# Main.net
KiCad netlist of a schematic drawn in Altium Designer
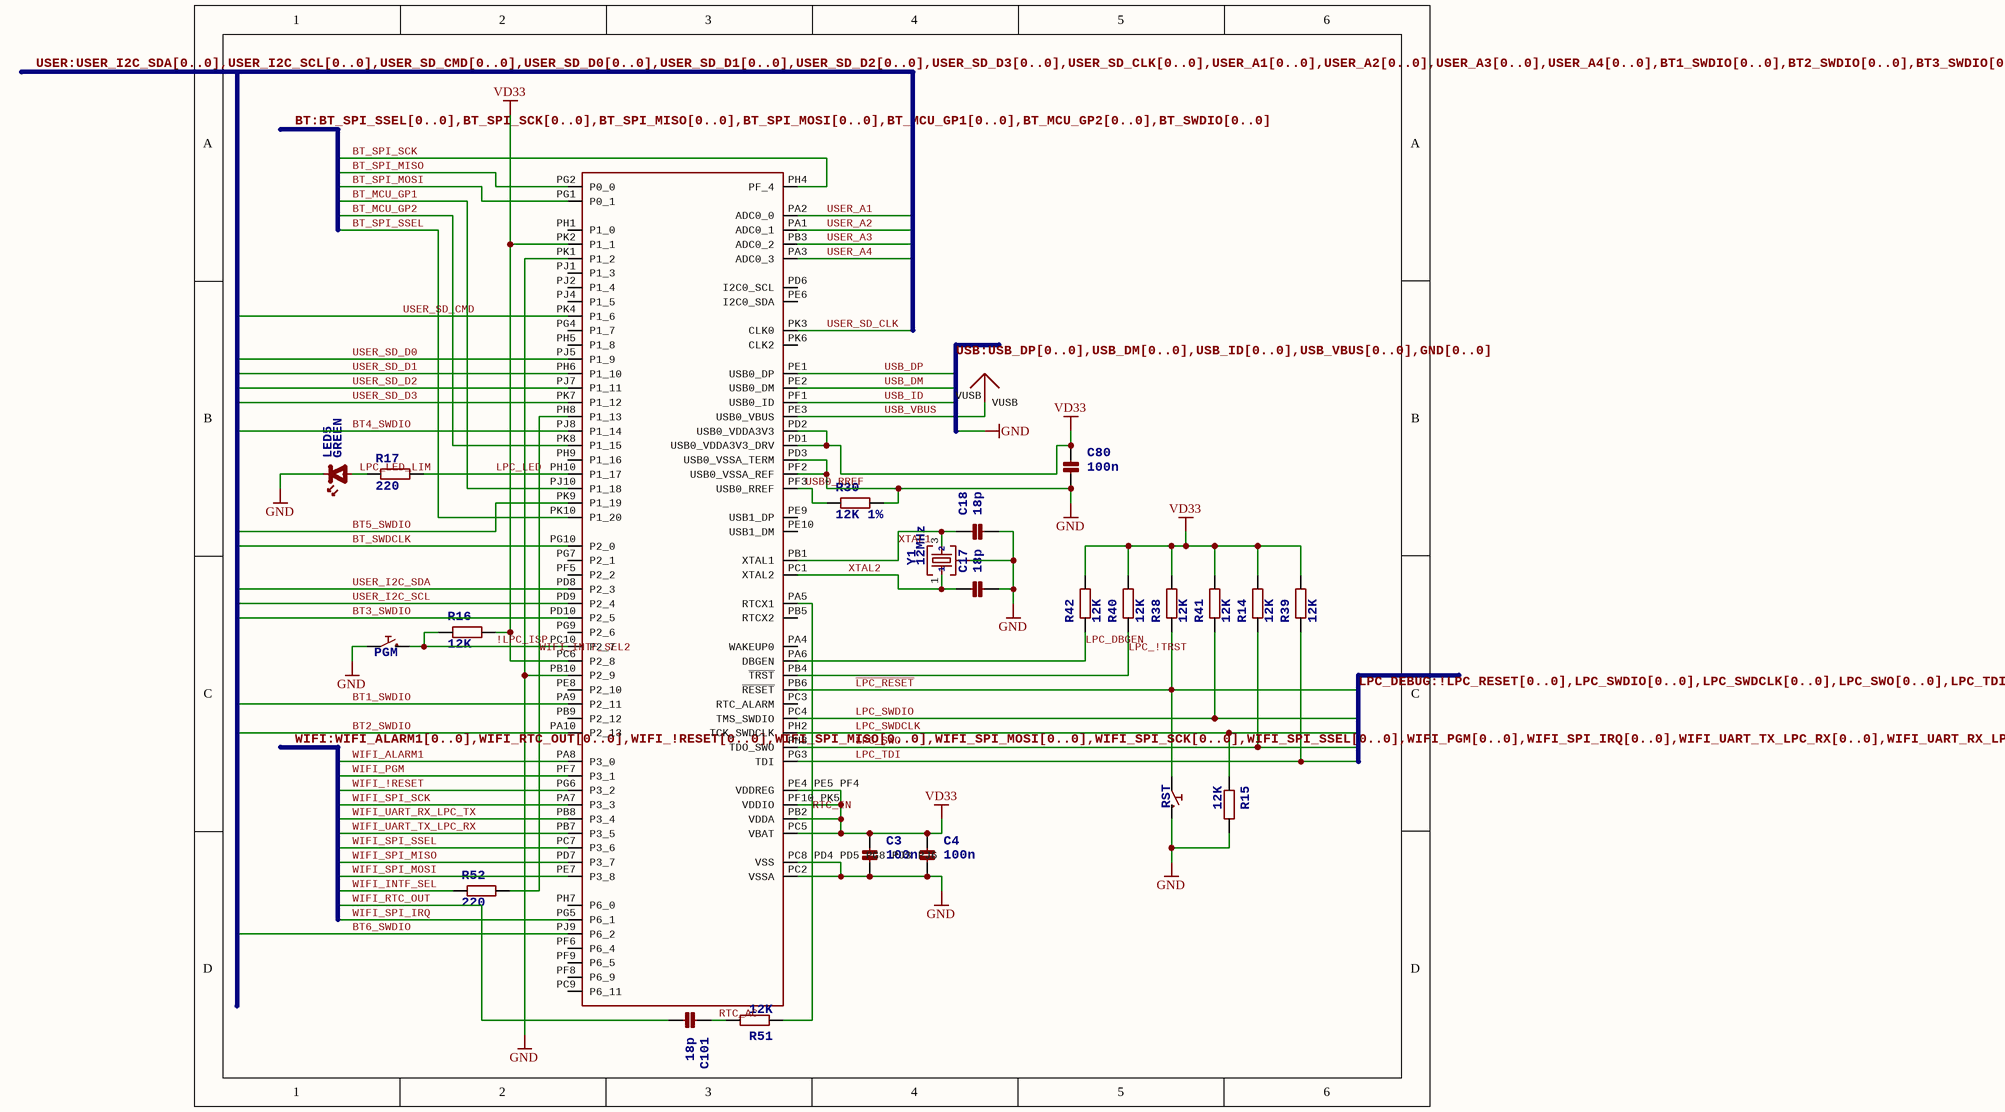
[diagram p0: Main.SchDoc]

(export (version "E")
  (design (tool "Eeschema 10.0.6"))
  (components
    (comp (ref "C3") (value "100n") (footprint "0402") (libsource (lib "") (part "CAP_CERAMIC0402_1")))
    (comp (ref "C4") (value "100n") (footprint "0402") (libsource (lib "") (part "CAP_CERAMIC0402_1")))
    (comp (ref "C17") (value "18p") (footprint "0402") (libsource (lib "anykey") (part "CAP_CERAMIC0402")))
    (comp (ref "C18") (value "18p") (footprint "0402") (libsource (lib "anykey") (part "CAP_CERAMIC0402")))
    (comp (ref "C80") (value "100n") (footprint "0402") (libsource (lib "") (part "CAP_CERAMIC0402_1")))
    (comp (ref "C101") (value "18p") (footprint "0402") (libsource (lib "") (part "CAP_CERAMIC0402_2")))
    (comp (ref "LED5")
      (value "GREEN")
      (footprint "0402_POLAR")
      (description "LED common")
      (libsource (lib "anykey") (part "LED0402"))
    )
    (comp (ref "MCU1")
      (value "LPC1837JET100TFBGA100(JET100)")
      (footprint "BGA100-0.8")
      (libsource (lib "anykey") (part "LPC1837JET100TFBGA100(JET100)"))
    )
    (comp (ref "PGM")
      (value "PUSHBUTTONKMR2XX")
      (footprint "CK-KMR2")
      (description "<p><b>Push button</b> 1 x momentary close switches</p>")
      (libsource (lib "anykey") (part "PUSHBUTTONKMR2XX"))
    )
    (comp (ref "R14")
      (value "12K")
      (footprint "0402")
      (description "<B>RESISTOR</B>, European symbol")
      (libsource (lib "anykey") (part "R-EU_0402"))
    )
    (comp (ref "R15")
      (value "12K")
      (footprint "0402")
      (description "<B>RESISTOR</B>, European symbol")
      (libsource (lib "anykey") (part "R-EU_0402"))
    )
    (comp (ref "R16")
      (value "12K")
      (footprint "0402")
      (description "<B>RESISTOR</B>, European symbol")
      (libsource (lib "anykey") (part "R-EU_0402"))
    )
    (comp (ref "R17")
      (value "220")
      (footprint "0402")
      (description "<B>RESISTOR</B>, European symbol")
      (libsource (lib "anykey") (part "R-EU_0402"))
    )
    (comp (ref "R30")
      (value "12K 1%")
      (footprint "0402")
      (description "<B>RESISTOR</B>, European symbol")
      (libsource (lib "anykey") (part "R-EU_0402"))
    )
    (comp (ref "R38")
      (value "12K")
      (footprint "0402")
      (description "<B>RESISTOR</B>, European symbol")
      (libsource (lib "anykey") (part "R-EU_0402"))
    )
    (comp (ref "R39")
      (value "12K")
      (footprint "0402")
      (description "<B>RESISTOR</B>, European symbol")
      (libsource (lib "anykey") (part "R-EU_0402"))
    )
    (comp (ref "R40")
      (value "12K")
      (footprint "0402")
      (description "<B>RESISTOR</B>, European symbol")
      (libsource (lib "anykey") (part "R-EU_0402"))
    )
    (comp (ref "R41")
      (value "12K")
      (footprint "0402")
      (description "<B>RESISTOR</B>, European symbol")
      (libsource (lib "anykey") (part "R-EU_0402"))
    )
    (comp (ref "R42")
      (value "12K")
      (footprint "0402")
      (description "<B>RESISTOR</B>, European symbol")
      (libsource (lib "anykey") (part "R-EU_0402"))
    )
    (comp (ref "R51")
      (value "12K")
      (footprint "0402")
      (description "<B>RESISTOR</B>, European symbol")
      (libsource (lib "anykey") (part "R-EU_0402"))
    )
    (comp (ref "R52")
      (value "220")
      (footprint "0402")
      (description "<B>RESISTOR</B>, European symbol")
      (libsource (lib "anykey") (part "R-EU_0402"))
    )
    (comp (ref "RST")
      (value "PUSHBUTTONKMR2XX")
      (footprint "CK-KMR2")
      (description "<p><b>Push button</b> 1 x momentary close switches</p>")
      (libsource (lib "anykey") (part "PUSHBUTTONKMR2XX"))
    )
    (comp (ref "U$31") (value "VUSB") (description "\"USB Power\"") (libsource (lib "anykey") (part "VUSB")))
    (comp (ref "Y1")
      (value "12MHz")
      (footprint "ABM8G")
      (fields (field (name "1") "1") (field (name "2") "2"))
      (libsource (lib "anykey") (part "CRYSTAL_WITH_GROUNDABM8G"))
    )
  )
  (nets
    (net (code "6") (name "/!LPC_ISP") (class "Default")
      (node (ref "MCU1") (pin "PC10") (pinfunction "P2_7_PC10") (pintype "passive"))
      (node (ref "PGM") (pin "P$3_P$4") (pinfunction "2_P$3_P$4") (pintype "passive"))
      (node (ref "R16") (pin "P$1") (pinfunction "1_P$1") (pintype "passive"))
    )
    (net (code "7") (name "/BT1_SWDIO") (class "Default")
      (node (ref "MCU1") (pin "PA9") (pinfunction "P2_11_PA9") (pintype "passive"))
    )
    (net (code "8") (name "/BT2_SWDIO") (class "Default")
      (node (ref "MCU1") (pin "PA10") (pinfunction "P2_13_PA10") (pintype "passive"))
    )
    (net (code "9") (name "/BT3_SWDIO") (class "Default")
      (node (ref "MCU1") (pin "PD10") (pinfunction "P2_5_PD10") (pintype "passive"))
    )
    (net (code "10") (name "/BT4_SWDIO") (class "Default")
      (node (ref "MCU1") (pin "PJ8") (pinfunction "P1_14_PJ8") (pintype "passive"))
    )
    (net (code "11") (name "/BT5_SWDIO") (class "Default")
      (node (ref "MCU1") (pin "PK9") (pinfunction "P1_19_PK9") (pintype "passive"))
    )
    (net (code "12") (name "/BT6_SWDIO") (class "Default")
      (node (ref "MCU1") (pin "PJ9") (pinfunction "P6_2_PJ9") (pintype "passive"))
    )
    (net (code "13") (name "/BT_MCU_GP1") (class "Default")
      (node (ref "MCU1") (pin "PJ10") (pinfunction "P1_18_PJ10") (pintype "passive"))
    )
    (net (code "14") (name "/BT_MCU_GP2") (class "Default")
      (node (ref "MCU1") (pin "PK8") (pinfunction "P1_15_PK8") (pintype "passive"))
    )
    (net (code "15") (name "/BT_SPI_MISO") (class "Default")
      (node (ref "MCU1") (pin "PG2") (pinfunction "P0_0_PG2") (pintype "passive"))
    )
    (net (code "16") (name "/BT_SPI_MOSI") (class "Default")
      (node (ref "MCU1") (pin "PG1") (pinfunction "P0_1_PG1") (pintype "passive"))
    )
    (net (code "17") (name "/BT_SPI_SCK") (class "Default")
      (node (ref "MCU1") (pin "PH4") (pinfunction "PF_4_PH4") (pintype "passive"))
    )
    (net (code "18") (name "/BT_SPI_SSEL") (class "Default")
      (node (ref "MCU1") (pin "PK10") (pinfunction "P1_20_PK10") (pintype "passive"))
    )
    (net (code "19") (name "/BT_SWDCLK") (class "Default")
      (node (ref "MCU1") (pin "PG10") (pinfunction "P2_0_PG10") (pintype "passive"))
    )
    (net (code "20") (name "/LPC_!TRST") (class "Default")
      (node (ref "MCU1") (pin "PB4") (pinfunction "~{TRST}_PB4") (pintype "passive"))
      (node (ref "R40") (pin "P$1") (pinfunction "1_P$1") (pintype "passive"))
    )
    (net (code "21") (name "/LPC_DBGEN") (class "Default")
      (node (ref "MCU1") (pin "PA6") (pinfunction "DBGEN_PA6") (pintype "passive"))
      (node (ref "R42") (pin "P$1") (pinfunction "1_P$1") (pintype "passive"))
    )
    (net (code "22") (name "/LPC_LED") (class "Default")
      (node (ref "MCU1") (pin "PH10") (pinfunction "P1_17_PH10") (pintype "passive"))
      (node (ref "R17") (pin "P$2") (pinfunction "2_P$2") (pintype "passive"))
    )
    (net (code "23") (name "/LPC_LED_LIM") (class "Default")
      (node (ref "LED5") (pin "A") (pinfunction "ANODE_A") (pintype "passive"))
      (node (ref "R17") (pin "P$1") (pinfunction "1_P$1") (pintype "passive"))
    )
    (net (code "24") (name "/LPC_SWDCLK") (class "Default")
      (node (ref "MCU1") (pin "PH2") (pinfunction "TCK_SWDCLK_PH2") (pintype "passive"))
      (node (ref "R15") (pin "P$1") (pinfunction "1_P$1") (pintype "passive"))
    )
    (net (code "25") (name "/LPC_SWDIO") (class "Default")
      (node (ref "MCU1") (pin "PC4") (pinfunction "TMS_SWDIO_PC4") (pintype "passive"))
      (node (ref "R41") (pin "P$1") (pinfunction "1_P$1") (pintype "passive"))
    )
    (net (code "26") (name "/LPC_SWO") (class "Default")
      (node (ref "MCU1") (pin "PH3") (pinfunction "TDO_SWO_PH3") (pintype "passive"))
      (node (ref "R14") (pin "P$1") (pinfunction "1_P$1") (pintype "passive"))
    )
    (net (code "27") (name "/LPC_TDI") (class "Default")
      (node (ref "MCU1") (pin "PG3") (pinfunction "TDI_PG3") (pintype "passive"))
      (node (ref "R39") (pin "P$1") (pinfunction "1_P$1") (pintype "passive"))
    )
    (net (code "28") (name "/RTC_AC") (class "Default")
      (node (ref "C101") (pin "P$1") (pinfunction "P$1_P$1") (pintype "passive"))
      (node (ref "R51") (pin "P$2") (pinfunction "2_P$2") (pintype "passive"))
    )
    (net (code "29") (name "/RTC_IN") (class "Default")
      (node (ref "MCU1") (pin "PA5") (pinfunction "RTCX1_PA5") (pintype "passive"))
      (node (ref "R51") (pin "P$1") (pinfunction "1_P$1") (pintype "passive"))
    )
    (net (code "30") (name "/USB0_RREF") (class "Default")
      (node (ref "MCU1") (pin "PF3") (pinfunction "USB0_RREF_PF3") (pintype "passive"))
      (node (ref "R30") (pin "P$1") (pinfunction "1_P$1") (pintype "passive"))
    )
    (net (code "31") (name "/USB_DM") (class "Default")
      (node (ref "MCU1") (pin "PE2") (pinfunction "USB0_DM_PE2") (pintype "passive"))
    )
    (net (code "32") (name "/USB_DP") (class "Default")
      (node (ref "MCU1") (pin "PE1") (pinfunction "USB0_DP_PE1") (pintype "passive"))
    )
    (net (code "33") (name "/USB_ID") (class "Default")
      (node (ref "MCU1") (pin "PF1") (pinfunction "USB0_ID_PF1") (pintype "passive"))
    )
    (net (code "34") (name "/USB_VBUS") (class "Default")
      (node (ref "MCU1") (pin "PE3") (pinfunction "USB0_VBUS_PE3") (pintype "passive"))
      (node (ref "U$31") (pin "VUSB") (pinfunction "VUSB_VUSB") (pintype "open_emitter"))
    )
    (net (code "35") (name "/USER_A1") (class "Default")
      (node (ref "MCU1") (pin "PA2") (pinfunction "ADC0_0_PA2") (pintype "passive"))
    )
    (net (code "36") (name "/USER_A2") (class "Default")
      (node (ref "MCU1") (pin "PA1") (pinfunction "ADC0_1_PA1") (pintype "passive"))
    )
    (net (code "37") (name "/USER_A3") (class "Default")
      (node (ref "MCU1") (pin "PB3") (pinfunction "ADC0_2_PB3") (pintype "passive"))
    )
    (net (code "38") (name "/USER_A4") (class "Default")
      (node (ref "MCU1") (pin "PA3") (pinfunction "ADC0_3_PA3") (pintype "passive"))
    )
    (net (code "39") (name "/USER_I2C_SCL") (class "Default")
      (node (ref "MCU1") (pin "PD9") (pinfunction "P2_4_PD9") (pintype "passive"))
    )
    (net (code "40") (name "/USER_I2C_SDA") (class "Default")
      (node (ref "MCU1") (pin "PD8") (pinfunction "P2_3_PD8") (pintype "passive"))
    )
    (net (code "41") (name "/USER_SD_CLK") (class "Default")
      (node (ref "MCU1") (pin "PK3") (pinfunction "CLK0_PK3") (pintype "passive"))
    )
    (net (code "42") (name "/USER_SD_CMD") (class "Default")
      (node (ref "MCU1") (pin "PK4") (pinfunction "P1_6_PK4") (pintype "passive"))
    )
    (net (code "43") (name "/USER_SD_D0") (class "Default")
      (node (ref "MCU1") (pin "PJ5") (pinfunction "P1_9_PJ5") (pintype "passive"))
    )
    (net (code "44") (name "/USER_SD_D1") (class "Default")
      (node (ref "MCU1") (pin "PH6") (pinfunction "P1_10_PH6") (pintype "passive"))
    )
    (net (code "45") (name "/USER_SD_D2") (class "Default")
      (node (ref "MCU1") (pin "PJ7") (pinfunction "P1_11_PJ7") (pintype "passive"))
    )
    (net (code "46") (name "/USER_SD_D3") (class "Default")
      (node (ref "MCU1") (pin "PK7") (pinfunction "P1_12_PK7") (pintype "passive"))
    )
    (net (code "47") (name "/WIFI_!RESET") (class "Default")
      (node (ref "MCU1") (pin "PG6") (pinfunction "P3_2_PG6") (pintype "passive"))
    )
    (net (code "48") (name "/WIFI_ALARM1") (class "Default")
      (node (ref "MCU1") (pin "PA8") (pinfunction "P3_0_PA8") (pintype "passive"))
    )
    (net (code "49") (name "/WIFI_INTF_SEL") (class "Default")
      (node (ref "R52") (pin "P$1") (pinfunction "1_P$1") (pintype "passive"))
    )
    (net (code "50") (name "/WIFI_INTF_SEL2") (class "Default")
      (node (ref "MCU1") (pin "PH8") (pinfunction "P1_13_PH8") (pintype "passive"))
      (node (ref "R52") (pin "P$2") (pinfunction "2_P$2") (pintype "passive"))
    )
    (net (code "51") (name "/WIFI_PGM") (class "Default")
      (node (ref "MCU1") (pin "PF7") (pinfunction "P3_1_PF7") (pintype "passive"))
    )
    (net (code "52") (name "/WIFI_RTC_OUT") (class "Default")
      (node (ref "C101") (pin "P$2") (pinfunction "P$2_P$2") (pintype "passive"))
    )
    (net (code "53") (name "/WIFI_SPI_IRQ") (class "Default")
      (node (ref "MCU1") (pin "PG5") (pinfunction "P6_1_PG5") (pintype "passive"))
    )
    (net (code "54") (name "/WIFI_SPI_MISO") (class "Default")
      (node (ref "MCU1") (pin "PD7") (pinfunction "P3_7_PD7") (pintype "passive"))
    )
    (net (code "55") (name "/WIFI_SPI_MOSI") (class "Default")
      (node (ref "MCU1") (pin "PE7") (pinfunction "P3_8_PE7") (pintype "passive"))
    )
    (net (code "56") (name "/WIFI_SPI_SCK") (class "Default")
      (node (ref "MCU1") (pin "PA7") (pinfunction "P3_3_PA7") (pintype "passive"))
    )
    (net (code "57") (name "/WIFI_SPI_SSEL") (class "Default")
      (node (ref "MCU1") (pin "PC7") (pinfunction "P3_6_PC7") (pintype "passive"))
    )
    (net (code "58") (name "/WIFI_UART_RX_LPC_TX") (class "Default")
      (node (ref "MCU1") (pin "PB8") (pinfunction "P3_4_PB8") (pintype "passive"))
    )
    (net (code "59") (name "/WIFI_UART_TX_LPC_RX") (class "Default")
      (node (ref "MCU1") (pin "PB7") (pinfunction "P3_5_PB7") (pintype "passive"))
    )
    (net (code "60") (name "/XTAL1") (class "Default")
      (node (ref "C18") (pin "P$1") (pinfunction "P$1_P$1") (pintype "passive"))
      (node (ref "MCU1") (pin "PB1") (pinfunction "XTAL1_PB1") (pintype "passive"))
      (node (ref "Y1") (pin "3") (pinfunction "2_3") (pintype "passive"))
    )
    (net (code "61") (name "/XTAL2") (class "Default")
      (node (ref "C17") (pin "P$1") (pinfunction "P$1_P$1") (pintype "passive"))
      (node (ref "MCU1") (pin "PC1") (pinfunction "XTAL2_PC1") (pintype "passive"))
      (node (ref "Y1") (pin "1") (pinfunction "1_1") (pintype "passive"))
    )
    (net (code "63") (name "/{\"LPC_DEBUG:!LPC_RESET[0..0],LPC_SWDIO[0..0],LPC_SWDCLK[0..0],LPC_SWO[0..0],LPC_TDI[0..0]\"}") (class "Default")
      (node (ref "MCU1") (pin "PB6") (pinfunction "~{RESET}_PB6") (pintype "passive"))
      (node (ref "R38") (pin "P$1") (pinfunction "1_P$1") (pintype "passive"))
      (node (ref "RST") (pin "P$1_P$2") (pinfunction "1_P$1_P$2") (pintype "passive"))
    )
    (net (code "67") (name "GND") (class "Default")
      (node (ref "C17") (pin "P$2") (pinfunction "P$2_P$2") (pintype "passive"))
      (node (ref "C18") (pin "P$2") (pinfunction "P$2_P$2") (pintype "passive"))
      (node (ref "C3") (pin "P$2") (pinfunction "P$2_P$2") (pintype "passive"))
      (node (ref "C4") (pin "P$2") (pinfunction "P$2_P$2") (pintype "passive"))
      (node (ref "C80") (pin "P$2") (pinfunction "P$2_P$2") (pintype "passive"))
      (node (ref "LED5") (pin "K") (pinfunction "CATHODE_K") (pintype "passive"))
      (node (ref "MCU1") (pin "PB10") (pinfunction "P2_9_PB10") (pintype "passive"))
      (node (ref "MCU1") (pin "PC2") (pinfunction "VSSA_PC2") (pintype "passive"))
      (node (ref "MCU1") (pin "PC8_PD4_PD5_PG8_PJ3_PJ6") (pinfunction "VSS_PC8_PD4_PD5_PG8_PJ3_PJ6") (pintype "passive"))
      (node (ref "MCU1") (pin "PD3") (pinfunction "USB0_VSSA_TERM_PD3") (pintype "power_in"))
      (node (ref "MCU1") (pin "PF2") (pinfunction "USB0_VSSA_REF_PF2") (pintype "power_in"))
      (node (ref "MCU1") (pin "PK1") (pinfunction "P1_2_PK1") (pintype "passive"))
      (node (ref "PGM") (pin "P$1_P$2") (pinfunction "1_P$1_P$2") (pintype "passive"))
      (node (ref "R15") (pin "P$2") (pinfunction "2_P$2") (pintype "passive"))
      (node (ref "R30") (pin "P$2") (pinfunction "2_P$2") (pintype "passive"))
      (node (ref "RST") (pin "P$3_P$4") (pinfunction "2_P$3_P$4") (pintype "passive"))
      (node (ref "Y1") (pin "2_4") (pinfunction "GND_2_4") (pintype "power_in"))
    )
    (net (code "68") (name "VD33") (class "Default")
      (node (ref "C3") (pin "P$1") (pinfunction "P$1_P$1") (pintype "passive"))
      (node (ref "C4") (pin "P$1") (pinfunction "P$1_P$1") (pintype "passive"))
      (node (ref "C80") (pin "P$1") (pinfunction "P$1_P$1") (pintype "passive"))
      (node (ref "MCU1") (pin "PB2") (pinfunction "VDDA_PB2") (pintype "passive"))
      (node (ref "MCU1") (pin "PC5") (pinfunction "VBAT_PC5") (pintype "passive"))
      (node (ref "MCU1") (pin "PC6") (pinfunction "P2_8_PC6") (pintype "passive"))
      (node (ref "MCU1") (pin "PD1") (pinfunction "USB0_VDDA3V3_DRV_PD1") (pintype "power_in"))
      (node (ref "MCU1") (pin "PD2") (pinfunction "USB0_VDDA3V3_PD2") (pintype "power_in"))
      (node (ref "MCU1") (pin "PE4_PE5_PF4") (pinfunction "VDDREG_PE4_PE5_PF4") (pintype "passive"))
      (node (ref "MCU1") (pin "PF10_PK5") (pinfunction "VDDIO_PF10_PK5") (pintype "passive"))
      (node (ref "MCU1") (pin "PK2") (pinfunction "P1_1_PK2") (pintype "passive"))
      (node (ref "R14") (pin "P$2") (pinfunction "2_P$2") (pintype "passive"))
      (node (ref "R16") (pin "P$2") (pinfunction "2_P$2") (pintype "passive"))
      (node (ref "R38") (pin "P$2") (pinfunction "2_P$2") (pintype "passive"))
      (node (ref "R39") (pin "P$2") (pinfunction "2_P$2") (pintype "passive"))
      (node (ref "R40") (pin "P$2") (pinfunction "2_P$2") (pintype "passive"))
      (node (ref "R41") (pin "P$2") (pinfunction "2_P$2") (pintype "passive"))
      (node (ref "R42") (pin "P$2") (pinfunction "2_P$2") (pintype "passive"))
    )
    (net (code "69") (name "unconnected-(MCU1-CLK2-PadPK6)") (class "Default")
      (node (ref "MCU1") (pin "PK6") (pinfunction "CLK2_PK6") (pintype "passive"))
    )
    (net (code "70") (name "unconnected-(MCU1-I2C0_SCL-PadPD6)") (class "Default")
      (node (ref "MCU1") (pin "PD6") (pinfunction "I2C0_SCL_PD6") (pintype "passive"))
    )
    (net (code "71") (name "unconnected-(MCU1-I2C0_SDA-PadPE6)") (class "Default")
      (node (ref "MCU1") (pin "PE6") (pinfunction "I2C0_SDA_PE6") (pintype "passive"))
    )
    (net (code "72") (name "unconnected-(MCU1-P1_0-PadPH1)") (class "Default")
      (node (ref "MCU1") (pin "PH1") (pinfunction "P1_0_PH1") (pintype "passive"))
    )
    (net (code "73") (name "unconnected-(MCU1-P1_3-PadPJ1)") (class "Default")
      (node (ref "MCU1") (pin "PJ1") (pinfunction "P1_3_PJ1") (pintype "passive"))
    )
    (net (code "74") (name "unconnected-(MCU1-P1_4-PadPJ2)") (class "Default")
      (node (ref "MCU1") (pin "PJ2") (pinfunction "P1_4_PJ2") (pintype "passive"))
    )
    (net (code "75") (name "unconnected-(MCU1-P1_5-PadPJ4)") (class "Default")
      (node (ref "MCU1") (pin "PJ4") (pinfunction "P1_5_PJ4") (pintype "passive"))
    )
    (net (code "76") (name "unconnected-(MCU1-P1_7-PadPG4)") (class "Default")
      (node (ref "MCU1") (pin "PG4") (pinfunction "P1_7_PG4") (pintype "passive"))
    )
    (net (code "77") (name "unconnected-(MCU1-P1_8-PadPH5)") (class "Default")
      (node (ref "MCU1") (pin "PH5") (pinfunction "P1_8_PH5") (pintype "passive"))
    )
    (net (code "78") (name "unconnected-(MCU1-P1_16-PadPH9)") (class "Default")
      (node (ref "MCU1") (pin "PH9") (pinfunction "P1_16_PH9") (pintype "passive"))
    )
    (net (code "79") (name "unconnected-(MCU1-P2_1-PadPG7)") (class "Default")
      (node (ref "MCU1") (pin "PG7") (pinfunction "P2_1_PG7") (pintype "passive"))
    )
    (net (code "80") (name "unconnected-(MCU1-P2_2-PadPF5)") (class "Default")
      (node (ref "MCU1") (pin "PF5") (pinfunction "P2_2_PF5") (pintype "passive"))
    )
    (net (code "81") (name "unconnected-(MCU1-P2_6-PadPG9)") (class "Default")
      (node (ref "MCU1") (pin "PG9") (pinfunction "P2_6_PG9") (pintype "passive"))
    )
    (net (code "82") (name "unconnected-(MCU1-P2_10-PadPE8)") (class "Default")
      (node (ref "MCU1") (pin "PE8") (pinfunction "P2_10_PE8") (pintype "passive"))
    )
    (net (code "83") (name "unconnected-(MCU1-P2_12-PadPB9)") (class "Default")
      (node (ref "MCU1") (pin "PB9") (pinfunction "P2_12_PB9") (pintype "passive"))
    )
    (net (code "84") (name "unconnected-(MCU1-P6_0-PadPH7)") (class "Default")
      (node (ref "MCU1") (pin "PH7") (pinfunction "P6_0_PH7") (pintype "passive"))
    )
    (net (code "85") (name "unconnected-(MCU1-P6_4-PadPF6)") (class "Default")
      (node (ref "MCU1") (pin "PF6") (pinfunction "P6_4_PF6") (pintype "passive"))
    )
    (net (code "86") (name "unconnected-(MCU1-P6_5-PadPF9)") (class "Default")
      (node (ref "MCU1") (pin "PF9") (pinfunction "P6_5_PF9") (pintype "passive"))
    )
    (net (code "87") (name "unconnected-(MCU1-P6_9-PadPF8)") (class "Default")
      (node (ref "MCU1") (pin "PF8") (pinfunction "P6_9_PF8") (pintype "passive"))
    )
    (net (code "88") (name "unconnected-(MCU1-P6_11-PadPC9)") (class "Default")
      (node (ref "MCU1") (pin "PC9") (pinfunction "P6_11_PC9") (pintype "passive"))
    )
    (net (code "89") (name "unconnected-(MCU1-RTCX2-PadPB5)") (class "Default")
      (node (ref "MCU1") (pin "PB5") (pinfunction "RTCX2_PB5") (pintype "passive"))
    )
    (net (code "90") (name "unconnected-(MCU1-RTC_ALARM-PadPC3)") (class "Default")
      (node (ref "MCU1") (pin "PC3") (pinfunction "RTC_ALARM_PC3") (pintype "passive"))
    )
    (net (code "91") (name "unconnected-(MCU1-USB1_DM-PadPE10)") (class "Default")
      (node (ref "MCU1") (pin "PE10") (pinfunction "USB1_DM_PE10") (pintype "passive"))
    )
    (net (code "92") (name "unconnected-(MCU1-USB1_DP-PadPE9)") (class "Default")
      (node (ref "MCU1") (pin "PE9") (pinfunction "USB1_DP_PE9") (pintype "passive"))
    )
    (net (code "93") (name "unconnected-(MCU1-WAKEUP0-PadPA4)") (class "Default")
      (node (ref "MCU1") (pin "PA4") (pinfunction "WAKEUP0_PA4") (pintype "passive"))
    )
  )
)
